# half-pint-turbidimeter_tsl230rd_tsl267_1.net
KiCad netlist of a schematic drawn in EAGLE
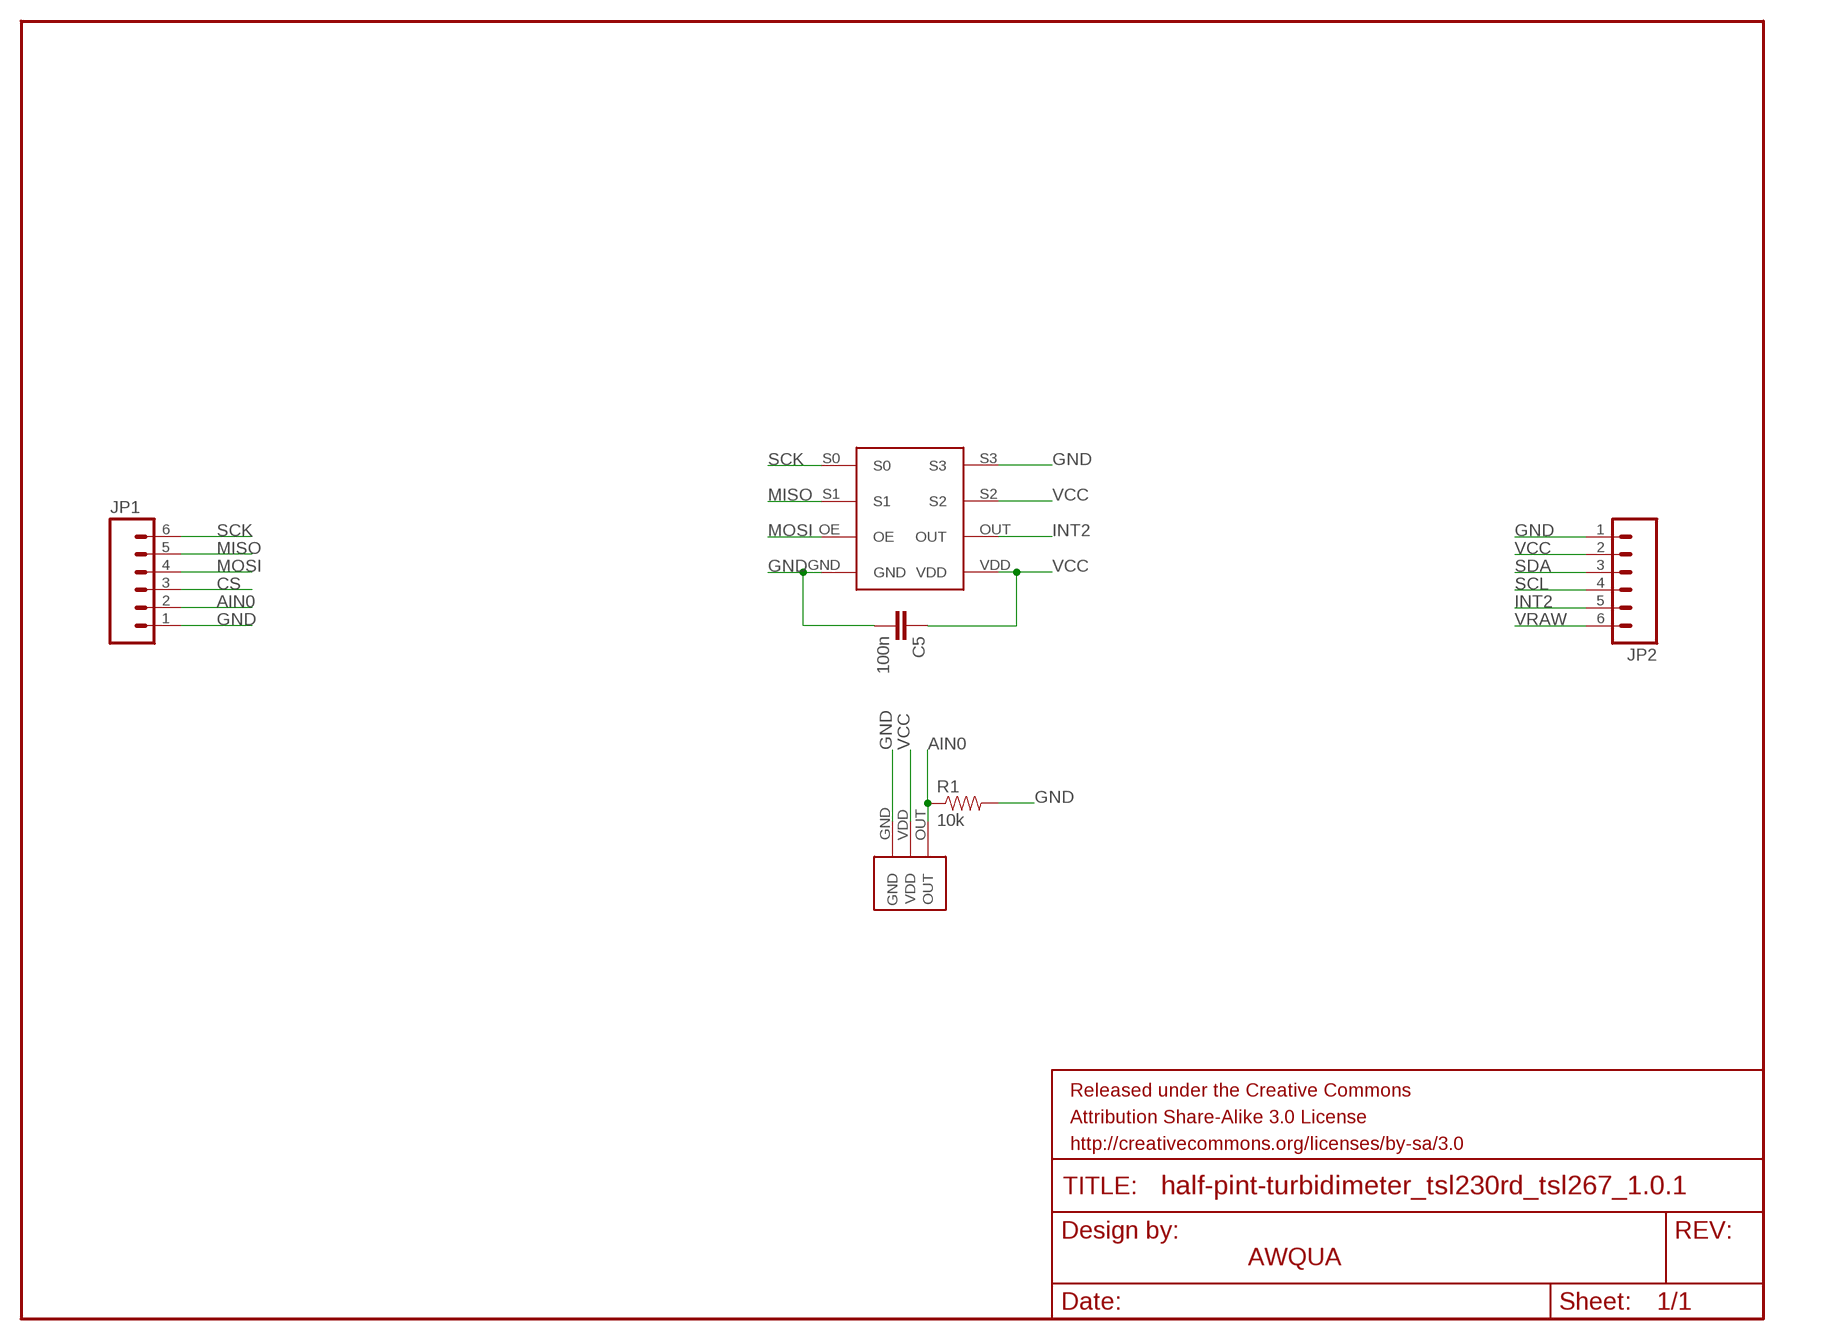
[diagram p0: schematic, sheet 1]

(export (version "E")
  (design (tool "Eeschema 10.0.6"))
  (components
    (comp (ref "C5")
      (value "100n")
      (footprint "eagle-import:0603-CAP")
      (libsource (lib "eagle-import") (part "CAP0603-CAP"))
    )
    (comp (ref "FRAME1")
      (value "FRAME-LETTER")
      (footprint "eagle-import:CREATIVE_COMMONS")
      (libsource (lib "eagle-import") (part "FRAME-LETTER"))
    )
    (comp (ref "JP1")
      (value "M06SIP")
      (footprint "eagle-import:1X06")
      (libsource (lib "eagle-import") (part "M06SIP"))
    )
    (comp (ref "JP2")
      (value "M06SIP")
      (footprint "eagle-import:1X06")
      (libsource (lib "eagle-import") (part "M06SIP"))
    )
    (comp (ref "R1")
      (value "10k")
      (footprint "eagle-import:0603-RES")
      (libsource (lib "eagle-import") (part "RESISTOR0603-RES"))
    )
    (comp (ref "U$1")
      (value "TSL267")
      (footprint "eagle-import:TSL267")
      (libsource (lib "eagle-import") (part "TSL267"))
    )
    (comp (ref "U$6")
      (value "TSL230RDSMD")
      (footprint "eagle-import:TSL230RD")
      (libsource (lib "eagle-import") (part "TSL230RDSMD"))
    )
  )
  (nets
    (net (code "1") (name "/AIN0") (class "Default")
      (node (ref "JP1") (pin "2") (pinfunction "2_2") (pintype "passive"))
      (node (ref "R1") (pin "1") (pinfunction "1_1") (pintype "passive"))
      (node (ref "U$1") (pin "OUT") (pinfunction "OUT_OUT") (pintype "bidirectional"))
    )
    (net (code "2") (name "/CS") (class "Default")
      (node (ref "JP1") (pin "3") (pinfunction "3_3") (pintype "passive"))
    )
    (net (code "3") (name "/GND") (class "Default")
      (node (ref "C5") (pin "2") (pinfunction "2_2") (pintype "passive"))
      (node (ref "JP1") (pin "1") (pinfunction "1_1") (pintype "passive"))
      (node (ref "JP2") (pin "1") (pinfunction "1_1") (pintype "passive"))
      (node (ref "R1") (pin "2") (pinfunction "2_2") (pintype "passive"))
      (node (ref "U$1") (pin "GND") (pinfunction "GND_GND") (pintype "bidirectional"))
      (node (ref "U$6") (pin "GND") (pinfunction "GND_GND") (pintype "bidirectional"))
      (node (ref "U$6") (pin "S3") (pinfunction "S3_S3") (pintype "bidirectional"))
    )
    (net (code "4") (name "/INT2") (class "Default")
      (node (ref "JP2") (pin "5") (pinfunction "5_5") (pintype "passive"))
      (node (ref "U$6") (pin "OUT") (pinfunction "OUT_OUT") (pintype "bidirectional"))
    )
    (net (code "5") (name "/MISO") (class "Default")
      (node (ref "JP1") (pin "5") (pinfunction "5_5") (pintype "passive"))
      (node (ref "U$6") (pin "S1") (pinfunction "S1_S1") (pintype "bidirectional"))
    )
    (net (code "6") (name "/MOSI") (class "Default")
      (node (ref "JP1") (pin "4") (pinfunction "4_4") (pintype "passive"))
      (node (ref "U$6") (pin "OE") (pinfunction "OE_OE") (pintype "bidirectional"))
    )
    (net (code "7") (name "/SCK") (class "Default")
      (node (ref "JP1") (pin "6") (pinfunction "6_6") (pintype "passive"))
      (node (ref "U$6") (pin "S0") (pinfunction "S0_S0") (pintype "bidirectional"))
    )
    (net (code "8") (name "/SCL") (class "Default")
      (node (ref "JP2") (pin "4") (pinfunction "4_4") (pintype "passive"))
    )
    (net (code "9") (name "/SDA") (class "Default")
      (node (ref "JP2") (pin "3") (pinfunction "3_3") (pintype "passive"))
    )
    (net (code "10") (name "/VCC") (class "Default")
      (node (ref "C5") (pin "1") (pinfunction "1_1") (pintype "passive"))
      (node (ref "JP2") (pin "2") (pinfunction "2_2") (pintype "passive"))
      (node (ref "U$1") (pin "VDD") (pinfunction "VDD_VDD") (pintype "bidirectional"))
      (node (ref "U$6") (pin "S2") (pinfunction "S2_S2") (pintype "bidirectional"))
      (node (ref "U$6") (pin "VDD") (pinfunction "VDD_VDD") (pintype "bidirectional"))
    )
    (net (code "11") (name "/VRAW") (class "Default")
      (node (ref "JP2") (pin "6") (pinfunction "6_6") (pintype "passive"))
    )
  )
)
